# 5-Accelerometer.net
KiCad netlist of a schematic drawn in Altium Designer
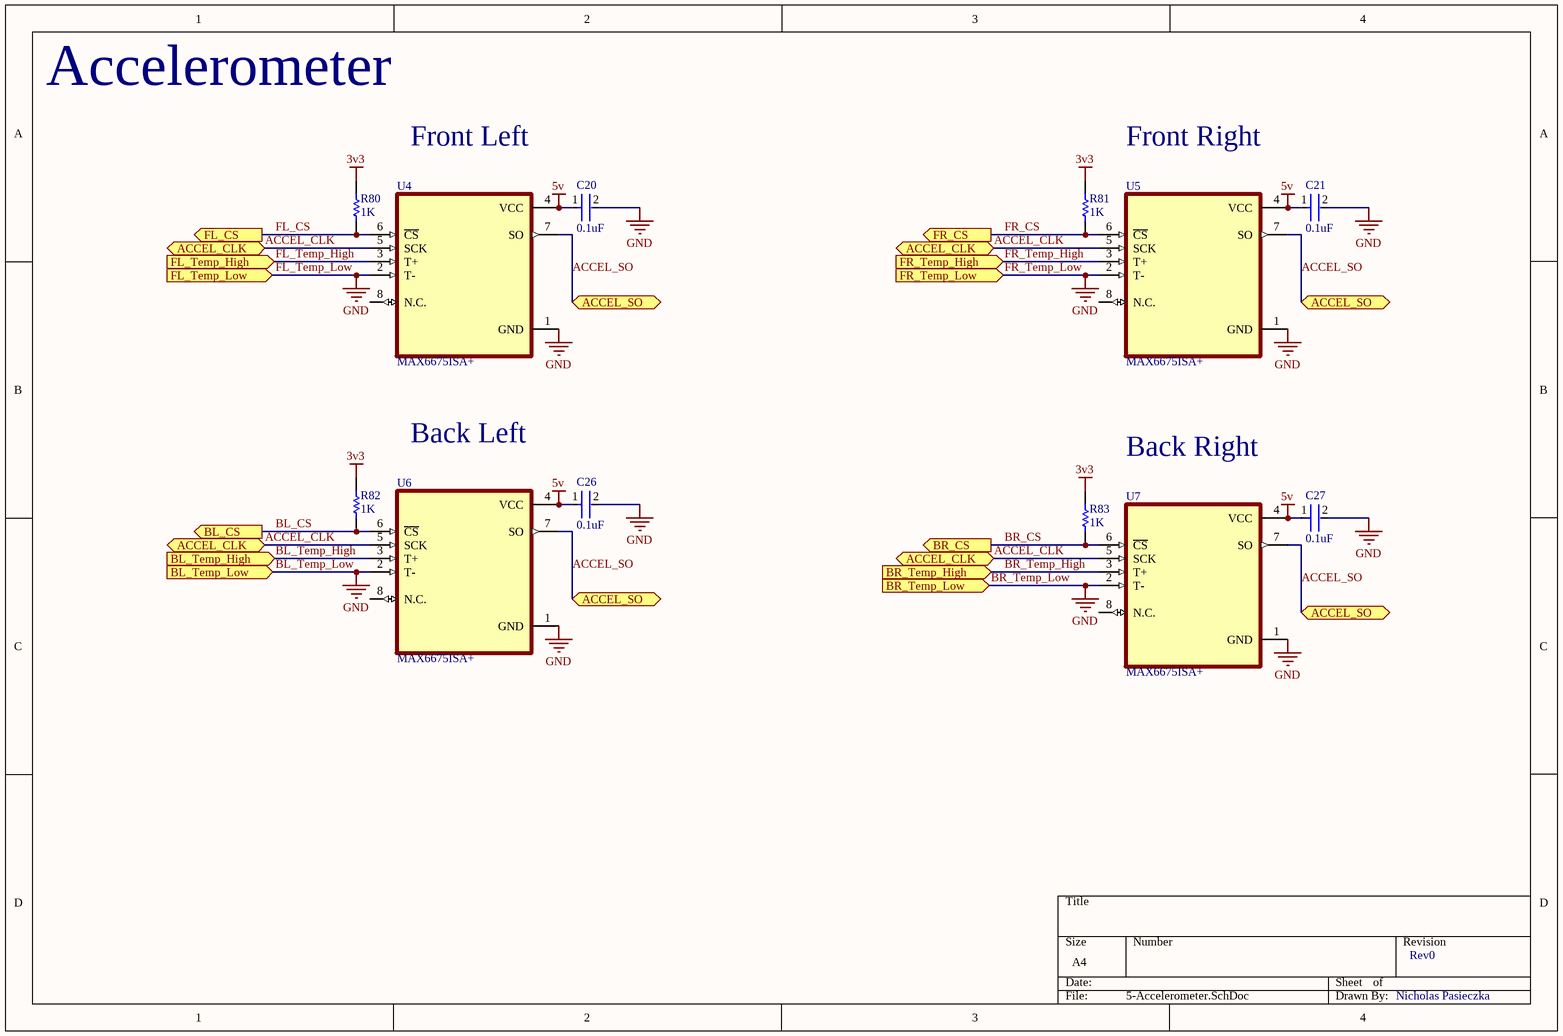
[diagram p0: 5-Accelerometer.SchDoc]

(export (version "E")
  (design (tool "Eeschema 10.0.6"))
  (components
    (comp (ref "C20")
      (value "0.1uF")
      (footprint "FP-CL17-IPC_C")
      (description "Cap Ceramic 100nF 10V X7R ±10% SMD 0402 +125°C Paper T/R")
      (fields (field (name "TOLERANCE") "10%"))
      (libsource (lib "Altium Content Vault") (part "b4654b650e69147ec39a6b967a45e02"))
    )
    (comp (ref "C21")
      (value "0.1uF")
      (footprint "FP-CL17-IPC_C")
      (description "Cap Ceramic 100nF 10V X7R ±10% SMD 0402 +125°C Paper T/R")
      (fields (field (name "TOLERANCE") "10%"))
      (libsource (lib "Altium Content Vault") (part "b4654b650e69147ec39a6b967a45e02"))
    )
    (comp (ref "C26")
      (value "0.1uF")
      (footprint "FP-CL17-IPC_C")
      (description "Cap Ceramic 100nF 10V X7R ±10% SMD 0402 +125°C Paper T/R")
      (fields (field (name "TOLERANCE") "10%"))
      (libsource (lib "Altium Content Vault") (part "b4654b650e69147ec39a6b967a45e02"))
    )
    (comp (ref "C27")
      (value "0.1uF")
      (footprint "FP-CL17-IPC_C")
      (description "Cap Ceramic 100nF 10V X7R ±10% SMD 0402 +125°C Paper T/R")
      (fields (field (name "TOLERANCE") "10%"))
      (libsource (lib "Altium Content Vault") (part "b4654b650e69147ec39a6b967a45e02"))
    )
    (comp (ref "R80")
      (value "1K")
      (footprint "1608[0603]")
      (description "Resistor")
      (fields (field (name "Comment") "Res1") (field (name "PUBLISHER") "Altium Limited"))
      (libsource (lib "Miscellaneous Devices") (part "Res1"))
    )
    (comp (ref "R81")
      (value "1K")
      (footprint "1608[0603]")
      (description "Resistor")
      (fields (field (name "Comment") "Res1") (field (name "PUBLISHER") "Altium Limited"))
      (libsource (lib "Miscellaneous Devices") (part "Res1"))
    )
    (comp (ref "R82")
      (value "1K")
      (footprint "1608[0603]")
      (description "Resistor")
      (fields (field (name "Comment") "Res1") (field (name "PUBLISHER") "Altium Limited"))
      (libsource (lib "Miscellaneous Devices") (part "Res1"))
    )
    (comp (ref "R83")
      (value "1K")
      (footprint "1608[0603]")
      (description "Resistor")
      (fields (field (name "Comment") "Res1") (field (name "PUBLISHER") "Altium Limited"))
      (libsource (lib "Miscellaneous Devices") (part "Res1"))
    )
    (comp (ref "U4")
      (value "MAX6675ISA+")
      (footprint "SOIC127P600X175-8N")
      (description "IC THERMOCOUP TO DGTL 8-SOIC")
      (fields (field (name "MF") "Maxim Integrated"))
      (libsource (lib "MAX6675ISA_") (part "MAX6675ISA+"))
    )
    (comp (ref "U5")
      (value "MAX6675ISA+")
      (footprint "SOIC127P600X175-8N")
      (description "IC THERMOCOUP TO DGTL 8-SOIC")
      (fields (field (name "MF") "Maxim Integrated"))
      (libsource (lib "MAX6675ISA_") (part "MAX6675ISA+"))
    )
    (comp (ref "U6")
      (value "MAX6675ISA+")
      (footprint "SOIC127P600X175-8N")
      (description "IC THERMOCOUP TO DGTL 8-SOIC")
      (fields (field (name "MF") "Maxim Integrated"))
      (libsource (lib "MAX6675ISA_") (part "MAX6675ISA+"))
    )
    (comp (ref "U7")
      (value "MAX6675ISA+")
      (footprint "SOIC127P600X175-8N")
      (description "IC THERMOCOUP TO DGTL 8-SOIC")
      (fields (field (name "MF") "Maxim Integrated"))
      (libsource (lib "MAX6675ISA_") (part "MAX6675ISA+"))
    )
  )
  (nets
    (net (code "1") (name "/ACCEL_CLK") (class "Default")
      (node (ref "U4") (pin "5") (pinfunction "SCK_5") (pintype "input"))
      (node (ref "U5") (pin "5") (pinfunction "SCK_5") (pintype "input"))
      (node (ref "U6") (pin "5") (pinfunction "SCK_5") (pintype "input"))
      (node (ref "U7") (pin "5") (pinfunction "SCK_5") (pintype "input"))
    )
    (net (code "2") (name "/ACCEL_SO") (class "Default")
      (node (ref "U4") (pin "7") (pinfunction "SO_7") (pintype "output"))
      (node (ref "U5") (pin "7") (pinfunction "SO_7") (pintype "output"))
      (node (ref "U6") (pin "7") (pinfunction "SO_7") (pintype "output"))
      (node (ref "U7") (pin "7") (pinfunction "SO_7") (pintype "output"))
    )
    (net (code "3") (name "/BL_CS") (class "Default")
      (node (ref "R82") (pin "1") (pinfunction "1_1") (pintype "passive"))
      (node (ref "U6") (pin "6") (pinfunction "~{CS}_6") (pintype "input"))
    )
    (net (code "4") (name "/BL_Temp_High") (class "Default")
      (node (ref "U6") (pin "3") (pinfunction "T+_3") (pintype "input"))
    )
    (net (code "5") (name "/BR_CS") (class "Default")
      (node (ref "R83") (pin "1") (pinfunction "1_1") (pintype "passive"))
      (node (ref "U7") (pin "6") (pinfunction "~{CS}_6") (pintype "input"))
    )
    (net (code "6") (name "/BR_Temp_High") (class "Default")
      (node (ref "U7") (pin "3") (pinfunction "T+_3") (pintype "input"))
    )
    (net (code "7") (name "/FL_CS") (class "Default")
      (node (ref "R80") (pin "1") (pinfunction "1_1") (pintype "passive"))
      (node (ref "U4") (pin "6") (pinfunction "~{CS}_6") (pintype "input"))
    )
    (net (code "8") (name "/FL_Temp_High") (class "Default")
      (node (ref "U4") (pin "3") (pinfunction "T+_3") (pintype "input"))
    )
    (net (code "9") (name "/FR_CS") (class "Default")
      (node (ref "R81") (pin "1") (pinfunction "1_1") (pintype "passive"))
      (node (ref "U5") (pin "6") (pinfunction "~{CS}_6") (pintype "input"))
    )
    (net (code "10") (name "/FR_Temp_High") (class "Default")
      (node (ref "U5") (pin "3") (pinfunction "T+_3") (pintype "input"))
    )
    (net (code "11") (name "3v3") (class "Default")
      (node (ref "R80") (pin "2") (pinfunction "2_2") (pintype "passive"))
      (node (ref "R81") (pin "2") (pinfunction "2_2") (pintype "passive"))
      (node (ref "R82") (pin "2") (pinfunction "2_2") (pintype "passive"))
      (node (ref "R83") (pin "2") (pinfunction "2_2") (pintype "passive"))
    )
    (net (code "12") (name "5v") (class "Default")
      (node (ref "C20") (pin "1") (pinfunction "1_1") (pintype "passive"))
      (node (ref "C21") (pin "1") (pinfunction "1_1") (pintype "passive"))
      (node (ref "C26") (pin "1") (pinfunction "1_1") (pintype "passive"))
      (node (ref "C27") (pin "1") (pinfunction "1_1") (pintype "passive"))
      (node (ref "U4") (pin "4") (pinfunction "VCC_4") (pintype "power_in"))
      (node (ref "U5") (pin "4") (pinfunction "VCC_4") (pintype "power_in"))
      (node (ref "U6") (pin "4") (pinfunction "VCC_4") (pintype "power_in"))
      (node (ref "U7") (pin "4") (pinfunction "VCC_4") (pintype "power_in"))
    )
    (net (code "13") (name "GND") (class "Default")
      (node (ref "C20") (pin "2") (pinfunction "2_2") (pintype "passive"))
      (node (ref "C21") (pin "2") (pinfunction "2_2") (pintype "passive"))
      (node (ref "C26") (pin "2") (pinfunction "2_2") (pintype "passive"))
      (node (ref "C27") (pin "2") (pinfunction "2_2") (pintype "passive"))
      (node (ref "U4") (pin "1") (pinfunction "GND_1") (pintype "power_in"))
      (node (ref "U4") (pin "2") (pinfunction "T-_2") (pintype "input"))
      (node (ref "U5") (pin "1") (pinfunction "GND_1") (pintype "power_in"))
      (node (ref "U5") (pin "2") (pinfunction "T-_2") (pintype "input"))
      (node (ref "U6") (pin "1") (pinfunction "GND_1") (pintype "power_in"))
      (node (ref "U6") (pin "2") (pinfunction "T-_2") (pintype "input"))
      (node (ref "U7") (pin "1") (pinfunction "GND_1") (pintype "power_in"))
      (node (ref "U7") (pin "2") (pinfunction "T-_2") (pintype "input"))
    )
    (net (code "14") (name "unconnected-(U4-N.C.-Pad8)") (class "Default")
      (node (ref "U4") (pin "8") (pinfunction "N.C._8") (pintype "bidirectional"))
    )
    (net (code "15") (name "unconnected-(U5-N.C.-Pad8)") (class "Default")
      (node (ref "U5") (pin "8") (pinfunction "N.C._8") (pintype "bidirectional"))
    )
    (net (code "16") (name "unconnected-(U6-N.C.-Pad8)") (class "Default")
      (node (ref "U6") (pin "8") (pinfunction "N.C._8") (pintype "bidirectional"))
    )
    (net (code "17") (name "unconnected-(U7-N.C.-Pad8)") (class "Default")
      (node (ref "U7") (pin "8") (pinfunction "N.C._8") (pintype "bidirectional"))
    )
  )
)
